# RS485.net
KiCad netlist of a schematic drawn in Altium Designer
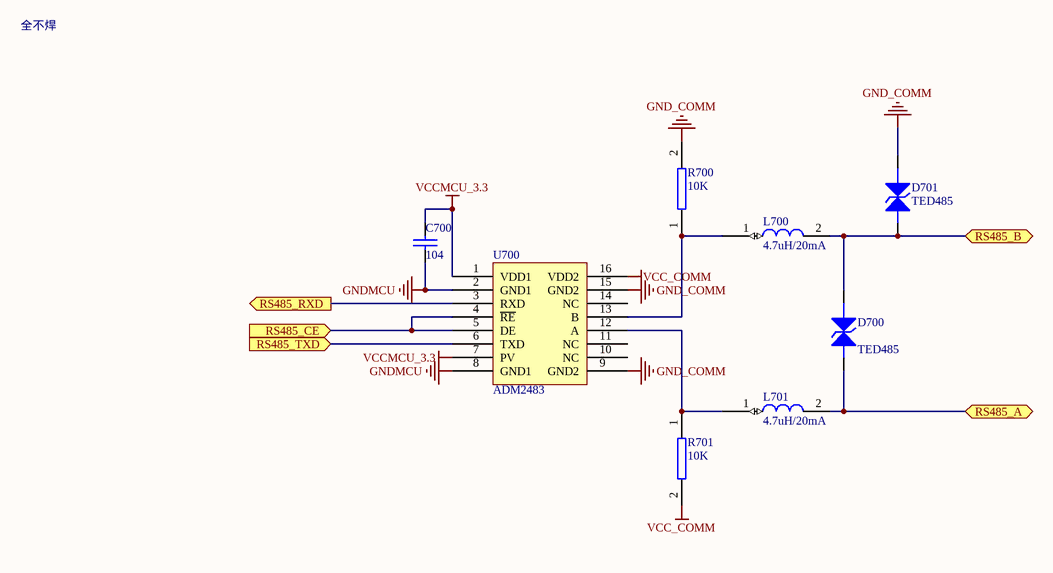
[diagram p0: RS485.SchDoc]

(export (version "E")
  (design (tool "Eeschema 10.0.6"))
  (components
    (comp (ref "C700")
      (value "104")
      (footprint "0805/C2")
      (description "Capacitor")
      (libsource (lib "YGInfoSCHLib") (part "CAP"))
    )
    (comp (ref "D700") (value "TED485") (footprint "TED485") (libsource (lib "YGInfoSCHLib") (part "TED485")))
    (comp (ref "D701") (value "TED485") (footprint "TED485") (libsource (lib "YGInfoSCHLib") (part "TED485")))
    (comp (ref "L700") (value "4.7uH/20mA") (footprint "1210") (libsource (lib "YGInfoSCHLib") (part "FUSE")))
    (comp (ref "L701") (value "4.7uH/20mA") (footprint "1210") (libsource (lib "YGInfoSCHLib") (part "FUSE")))
    (comp (ref "R700") (value "10K") (footprint "0805/R2") (libsource (lib "YGInfoSCHLib") (part "RES2")))
    (comp (ref "R701") (value "10K") (footprint "0805/R2") (libsource (lib "YGInfoSCHLib") (part "RES2")))
    (comp (ref "U700")
      (value "ADM2483")
      (footprint "ADM2483-16")
      (libsource (lib "YGInfoSCHLib") (part "RSM485CHT"))
    )
  )
  (nets
    (net (code "1") (name "/RS485_A") (class "Default")
      (node (ref "D700") (pin "1") (pinfunction "1_1") (pintype "passive"))
      (node (ref "L701") (pin "2") (pinfunction "2_2") (pintype "passive"))
    )
    (net (code "2") (name "/RS485_B") (class "Default")
      (node (ref "D700") (pin "2") (pinfunction "2_2") (pintype "passive"))
      (node (ref "D701") (pin "1") (pinfunction "1_1") (pintype "passive"))
      (node (ref "L700") (pin "2") (pinfunction "2_2") (pintype "passive"))
    )
    (net (code "3") (name "/RS485_CE") (class "Default")
      (node (ref "U700") (pin "4") (pinfunction "~{RE}_4") (pintype "passive"))
      (node (ref "U700") (pin "5") (pinfunction "DE_5") (pintype "passive"))
    )
    (net (code "4") (name "/RS485_RXD") (class "Default")
      (node (ref "U700") (pin "3") (pinfunction "RXD_3") (pintype "passive"))
    )
    (net (code "5") (name "/RS485_TXD") (class "Default")
      (node (ref "U700") (pin "6") (pinfunction "TXD_6") (pintype "passive"))
    )
    (net (code "6") (name "GNDMCU") (class "Default")
      (node (ref "C700") (pin "1") (pinfunction "1_1") (pintype "passive"))
      (node (ref "U700") (pin "2") (pinfunction "GND1_2") (pintype "passive"))
      (node (ref "U700") (pin "8") (pinfunction "GND1_8") (pintype "passive"))
    )
    (net (code "7") (name "GND_COMM") (class "Default")
      (node (ref "D701") (pin "2") (pinfunction "2_2") (pintype "passive"))
      (node (ref "R700") (pin "2") (pinfunction "2_2") (pintype "passive"))
      (node (ref "U700") (pin "15") (pinfunction "GND2_15") (pintype "passive"))
      (node (ref "U700") (pin "9") (pinfunction "GND2_9") (pintype "passive"))
    )
    (net (code "8") (name "Net-(U700-A)") (class "Default")
      (node (ref "L701") (pin "1") (pinfunction "1_1") (pintype "bidirectional"))
      (node (ref "R701") (pin "1") (pinfunction "1_1") (pintype "passive"))
      (node (ref "U700") (pin "12") (pinfunction "A_12") (pintype "passive"))
    )
    (net (code "9") (name "Net-(U700-B)") (class "Default")
      (node (ref "L700") (pin "1") (pinfunction "1_1") (pintype "bidirectional"))
      (node (ref "R700") (pin "1") (pinfunction "1_1") (pintype "passive"))
      (node (ref "U700") (pin "13") (pinfunction "B_13") (pintype "passive"))
    )
    (net (code "10") (name "VCCMCU_3.3") (class "Default")
      (node (ref "C700") (pin "2") (pinfunction "2_2") (pintype "passive"))
      (node (ref "U700") (pin "1") (pinfunction "VDD1_1") (pintype "passive"))
      (node (ref "U700") (pin "7") (pinfunction "PV_7") (pintype "passive"))
    )
    (net (code "11") (name "VCC_COMM") (class "Default")
      (node (ref "R701") (pin "2") (pinfunction "2_2") (pintype "passive"))
      (node (ref "U700") (pin "16") (pinfunction "VDD2_16") (pintype "passive"))
    )
    (net (code "12") (name "unconnected-(U700-NC-Pad10)") (class "Default")
      (node (ref "U700") (pin "10") (pinfunction "NC_10") (pintype "passive"))
    )
    (net (code "13") (name "unconnected-(U700-NC-Pad11)") (class "Default")
      (node (ref "U700") (pin "11") (pinfunction "NC_11") (pintype "passive"))
    )
    (net (code "14") (name "unconnected-(U700-NC-Pad14)") (class "Default")
      (node (ref "U700") (pin "14") (pinfunction "NC_14") (pintype "passive"))
    )
  )
)
